# fast_shutdown_v5_0.net
KiCad netlist of a schematic drawn in EAGLE
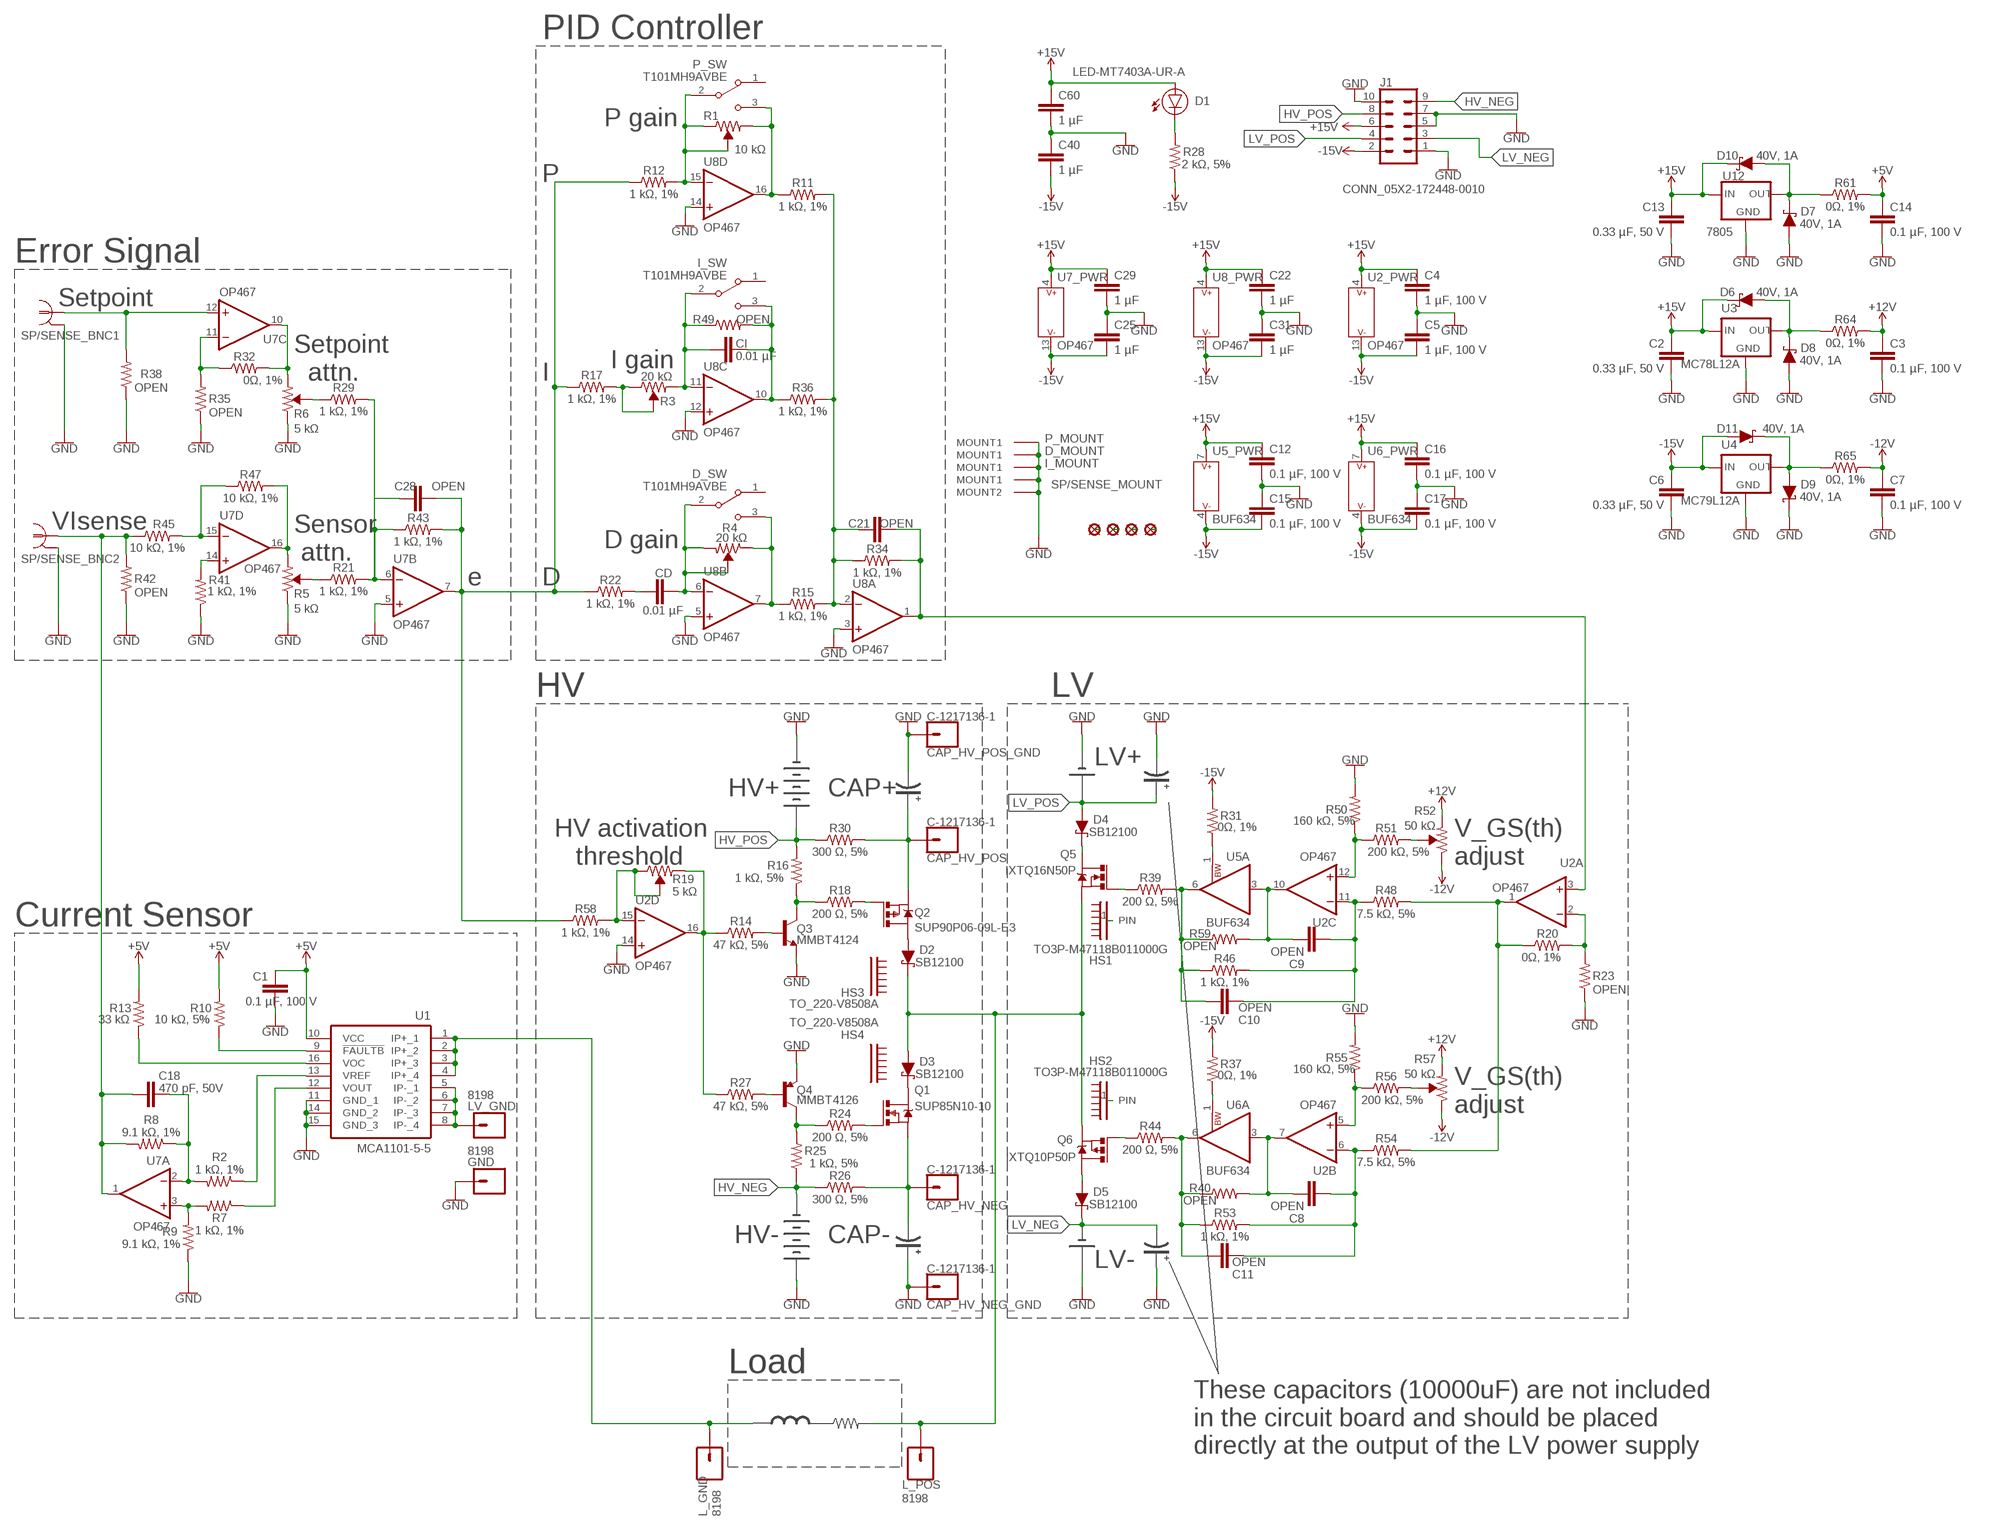
[diagram p0: schematic, sheet 1]

(export (version "E")
  (design (tool "Eeschema 10.0.6"))
  (components
    (comp (ref "C1")
      (value "0.1 µF, 100 V")
      (footprint "eagle-import:C1206")
      (fields (field (name "MFR") "KEMET"))
      (libsource (lib "eagle-import") (part "0.1µF-C1206C104J1RACTU"))
    )
    (comp (ref "C2")
      (value "0.33 µF, 50 V")
      (footprint "eagle-import:C1206")
      (fields (field (name "MFR") "Samsung Electro-Mechanics"))
      (libsource (lib "eagle-import") (part "0.33µF-CL31B334KBFNNNE"))
    )
    (comp (ref "C3")
      (value "0.1 µF, 100 V")
      (footprint "eagle-import:C1206")
      (fields (field (name "MFR") "KEMET"))
      (libsource (lib "eagle-import") (part "0.1µF-C1206C104J1RACTU"))
    )
    (comp (ref "C4")
      (value "1 µF, 100 V")
      (footprint "eagle-import:C1206")
      (fields (field (name "MFR") "KEMET"))
      (libsource (lib "eagle-import") (part "1µF-C1206X105J1RACTU"))
    )
    (comp (ref "C5")
      (value "1 µF, 100 V")
      (footprint "eagle-import:C1206")
      (fields (field (name "MFR") "KEMET"))
      (libsource (lib "eagle-import") (part "1µF-C1206X105J1RACTU"))
    )
    (comp (ref "C6")
      (value "0.33 µF, 50 V")
      (footprint "eagle-import:C1206")
      (fields (field (name "MFR") "Samsung Electro-Mechanics"))
      (libsource (lib "eagle-import") (part "0.33µF-CL31B334KBFNNNE"))
    )
    (comp (ref "C7")
      (value "0.1 µF, 100 V")
      (footprint "eagle-import:C1206")
      (fields (field (name "MFR") "KEMET"))
      (libsource (lib "eagle-import") (part "0.1µF-C1206C104J1RACTU"))
    )
    (comp (ref "C8")
      (value "OPEN")
      (footprint "eagle-import:C1206_OPEN")
      (fields (field (name "MFR") "NA"))
      (libsource (lib "eagle-import") (part "OPEN"))
    )
    (comp (ref "C9")
      (value "OPEN")
      (footprint "eagle-import:C1206_OPEN")
      (fields (field (name "MFR") "NA"))
      (libsource (lib "eagle-import") (part "OPEN"))
    )
    (comp (ref "C10")
      (value "OPEN")
      (footprint "eagle-import:C1206_OPEN")
      (fields (field (name "MFR") "NA"))
      (libsource (lib "eagle-import") (part "OPEN"))
    )
    (comp (ref "C11")
      (value "OPEN")
      (footprint "eagle-import:C1206_OPEN")
      (fields (field (name "MFR") "NA"))
      (libsource (lib "eagle-import") (part "OPEN"))
    )
    (comp (ref "C12")
      (value "0.1 µF, 100 V")
      (footprint "eagle-import:C1206")
      (fields (field (name "MFR") "KEMET"))
      (libsource (lib "eagle-import") (part "0.1µF-C1206C104J1RACTU"))
    )
    (comp (ref "C13")
      (value "0.33 µF, 50 V")
      (footprint "eagle-import:C1206")
      (fields (field (name "MFR") "Samsung Electro-Mechanics"))
      (libsource (lib "eagle-import") (part "0.33µF-CL31B334KBFNNNE"))
    )
    (comp (ref "C14")
      (value "0.1 µF, 100 V")
      (footprint "eagle-import:C1206")
      (fields (field (name "MFR") "KEMET"))
      (libsource (lib "eagle-import") (part "0.1µF-C1206C104J1RACTU"))
    )
    (comp (ref "C15")
      (value "0.1 µF, 100 V")
      (footprint "eagle-import:C1206")
      (fields (field (name "MFR") "KEMET"))
      (libsource (lib "eagle-import") (part "0.1µF-C1206C104J1RACTU"))
    )
    (comp (ref "C16")
      (value "0.1 µF, 100 V")
      (footprint "eagle-import:C1206")
      (fields (field (name "MFR") "KEMET"))
      (libsource (lib "eagle-import") (part "0.1µF-C1206C104J1RACTU"))
    )
    (comp (ref "C17")
      (value "0.1 µF, 100 V")
      (footprint "eagle-import:C1206")
      (fields (field (name "MFR") "KEMET"))
      (libsource (lib "eagle-import") (part "0.1µF-C1206C104J1RACTU"))
    )
    (comp (ref "C18")
      (value "470 pF, 50V")
      (footprint "eagle-import:C1206")
      (fields (field (name "MFR") "KEMET"))
      (libsource (lib "eagle-import") (part "470ρF-C1206C471K5RACTU"))
    )
    (comp (ref "C21")
      (value "OPEN")
      (footprint "eagle-import:C1206_OPEN")
      (fields (field (name "MFR") "NA"))
      (libsource (lib "eagle-import") (part "OPEN"))
    )
    (comp (ref "C22")
      (value "1 µF")
      (footprint "eagle-import:C1206")
      (fields (field (name "MFR") "KEMET"))
      (libsource (lib "eagle-import") (part "1µF-C1206C105K3RACTU"))
    )
    (comp (ref "C25")
      (value "1 µF")
      (footprint "eagle-import:C1206")
      (fields (field (name "MFR") "KEMET"))
      (libsource (lib "eagle-import") (part "1µF-C1206C105K3RACTU"))
    )
    (comp (ref "C28")
      (value "OPEN")
      (footprint "eagle-import:C1206_OPEN")
      (fields (field (name "MFR") "NA"))
      (libsource (lib "eagle-import") (part "OPEN"))
    )
    (comp (ref "C29")
      (value "1 µF")
      (footprint "eagle-import:C1206")
      (fields (field (name "MFR") "KEMET"))
      (libsource (lib "eagle-import") (part "1µF-C1206C105K3RACTU"))
    )
    (comp (ref "C31")
      (value "1 µF")
      (footprint "eagle-import:C1206")
      (fields (field (name "MFR") "KEMET"))
      (libsource (lib "eagle-import") (part "1µF-C1206C105K3RACTU"))
    )
    (comp (ref "C40")
      (value "1 µF")
      (footprint "eagle-import:C1206")
      (fields (field (name "MFR") "KEMET"))
      (libsource (lib "eagle-import") (part "1µF-C1206C105K3RACTU"))
    )
    (comp (ref "C60")
      (value "1 µF")
      (footprint "eagle-import:C1206")
      (fields (field (name "MFR") "KEMET"))
      (libsource (lib "eagle-import") (part "1µF-C1206C105K3RACTU"))
    )
    (comp (ref "CAP_HV_NEG")
      (value "C-1217136-1")
      (footprint "eagle-import:C-1217136-1")
      (fields (field (name "MFR") "AMP - TE CONNECTIVITY"))
      (libsource (lib "eagle-import") (part "C-1217136-1"))
    )
    (comp (ref "CAP_HV_NEG_GND")
      (value "C-1217136-1")
      (footprint "eagle-import:C-1217136-1")
      (fields (field (name "MFR") "AMP - TE CONNECTIVITY"))
      (libsource (lib "eagle-import") (part "C-1217136-1"))
    )
    (comp (ref "CAP_HV_POS")
      (value "C-1217136-1")
      (footprint "eagle-import:C-1217136-1")
      (fields (field (name "MFR") "AMP - TE CONNECTIVITY"))
      (libsource (lib "eagle-import") (part "C-1217136-1"))
    )
    (comp (ref "CAP_HV_POS_GND")
      (value "C-1217136-1")
      (footprint "eagle-import:C-1217136-1")
      (fields (field (name "MFR") "AMP - TE CONNECTIVITY"))
      (libsource (lib "eagle-import") (part "C-1217136-1"))
    )
    (comp (ref "CD")
      (value "0.01 µF")
      (footprint "eagle-import:C1206")
      (fields (field (name "MFR") "KEMET"))
      (libsource (lib "eagle-import") (part "0.01µF-C1206C103K1RACTU"))
    )
    (comp (ref "CI")
      (value "0.01 µF")
      (footprint "eagle-import:C1206")
      (fields (field (name "MFR") "KEMET"))
      (libsource (lib "eagle-import") (part "0.01µF-C1206C103K1RACTU"))
    )
    (comp (ref "D")
      (value "T101MH9AVBE")
      (footprint "eagle-import:T101MH9AVBE")
      (fields (field (name "MFR") "C&K"))
      (libsource (lib "eagle-import") (part "T101MH9AVBE"))
    )
    (comp (ref "D1")
      (value "LED-MT7403A-UR-A")
      (footprint "eagle-import:LED3MM")
      (fields (field (name "MFR") "Marktech Optoelectronics"))
      (libsource (lib "eagle-import") (part "LED-MT7403A-UR-A"))
    )
    (comp (ref "D2")
      (value "SB12100")
      (footprint "eagle-import:D5.4X7.5")
      (fields (field (name "MFR") "Diotec Semiconductor"))
      (libsource (lib "eagle-import") (part "DIODE_SCHOTTKY-SB12100"))
    )
    (comp (ref "D3")
      (value "SB12100")
      (footprint "eagle-import:D5.4X7.5")
      (fields (field (name "MFR") "Diotec Semiconductor"))
      (libsource (lib "eagle-import") (part "DIODE_SCHOTTKY-SB12100"))
    )
    (comp (ref "D4")
      (value "SB12100")
      (footprint "eagle-import:D5.4X7.5")
      (fields (field (name "MFR") "Diotec Semiconductor"))
      (libsource (lib "eagle-import") (part "DIODE_SCHOTTKY-SB12100"))
    )
    (comp (ref "D5")
      (value "SB12100")
      (footprint "eagle-import:D5.4X7.5")
      (fields (field (name "MFR") "Diotec Semiconductor"))
      (libsource (lib "eagle-import") (part "DIODE_SCHOTTKY-SB12100"))
    )
    (comp (ref "D6")
      (value "40V, 1A")
      (footprint "eagle-import:DO-214AC")
      (fields (field (name "MFR") "ROHM Semiconductor"))
      (libsource (lib "eagle-import") (part "DIODE_SCHOTTKY-RB168L-40TFTE25"))
    )
    (comp (ref "D7")
      (value "40V, 1A")
      (footprint "eagle-import:DO-214AC")
      (fields (field (name "MFR") "ROHM Semiconductor"))
      (libsource (lib "eagle-import") (part "DIODE_SCHOTTKY-RB168L-40TFTE25"))
    )
    (comp (ref "D8")
      (value "40V, 1A")
      (footprint "eagle-import:DO-214AC")
      (fields (field (name "MFR") "ROHM Semiconductor"))
      (libsource (lib "eagle-import") (part "DIODE_SCHOTTKY-RB168L-40TFTE25"))
    )
    (comp (ref "D9")
      (value "40V, 1A")
      (footprint "eagle-import:DO-214AC")
      (fields (field (name "MFR") "ROHM Semiconductor"))
      (libsource (lib "eagle-import") (part "DIODE_SCHOTTKY-RB168L-40TFTE25"))
    )
    (comp (ref "D10")
      (value "40V, 1A")
      (footprint "eagle-import:DO-214AC")
      (fields (field (name "MFR") "ROHM Semiconductor"))
      (libsource (lib "eagle-import") (part "DIODE_SCHOTTKY-RB168L-40TFTE25"))
    )
    (comp (ref "D11")
      (value "40V, 1A")
      (footprint "eagle-import:DO-214AC")
      (fields (field (name "MFR") "ROHM Semiconductor"))
      (libsource (lib "eagle-import") (part "DIODE_SCHOTTKY-RB168L-40TFTE25"))
    )
    (comp (ref "GND")
      (value "8198")
      (footprint "eagle-import:8198")
      (fields (field (name "MFR") "Keystone Electronics"))
      (libsource (lib "eagle-import") (part "8198"))
    )
    (comp (ref "HS1")
      (value "TO3P-M47118B011000G")
      (footprint "eagle-import:M47118B011000G")
      (fields (field (name "MFR") "Aavid"))
      (libsource (lib "eagle-import") (part "TO3P-M47118B011000G"))
    )
    (comp (ref "HS2")
      (value "TO3P-M47118B011000G")
      (footprint "eagle-import:M47118B011000G")
      (fields (field (name "MFR") "Aavid"))
      (libsource (lib "eagle-import") (part "TO3P-M47118B011000G"))
    )
    (comp (ref "HS3")
      (value "TO_220-V8508A")
      (footprint "eagle-import:V8508A")
      (fields (field (name "MFR") "Assmann WSW Components"))
      (libsource (lib "eagle-import") (part "TO_220-V8508A"))
    )
    (comp (ref "HS4")
      (value "TO_220-V8508A")
      (footprint "eagle-import:V8508A")
      (fields (field (name "MFR") "Assmann WSW Components"))
      (libsource (lib "eagle-import") (part "TO_220-V8508A"))
    )
    (comp (ref "I")
      (value "T101MH9AVBE")
      (footprint "eagle-import:T101MH9AVBE")
      (fields (field (name "MFR") "C&K"))
      (libsource (lib "eagle-import") (part "T101MH9AVBE"))
    )
    (comp (ref "J1")
      (value "CONN_05X2-172448-0010")
      (footprint "eagle-import:1724480010")
      (fields (field (name "MFR") "Molex"))
      (libsource (lib "eagle-import") (part "CONN_05X2-172448-0010"))
    )
    (comp (ref "LV_GND")
      (value "8198")
      (footprint "eagle-import:8198")
      (fields (field (name "MFR") "Keystone Electronics"))
      (libsource (lib "eagle-import") (part "8198"))
    )
    (comp (ref "L_GND")
      (value "8198")
      (footprint "eagle-import:8198")
      (fields (field (name "MFR") "Keystone Electronics"))
      (libsource (lib "eagle-import") (part "8198"))
    )
    (comp (ref "L_POS")
      (value "8198")
      (footprint "eagle-import:8198")
      (fields (field (name "MFR") "Keystone Electronics"))
      (libsource (lib "eagle-import") (part "8198"))
    )
    (comp (ref "P")
      (value "T101MH9AVBE")
      (footprint "eagle-import:T101MH9AVBE")
      (fields (field (name "MFR") "C&K"))
      (libsource (lib "eagle-import") (part "T101MH9AVBE"))
    )
    (comp (ref "P1")
      (value "PAD-M3.0")
      (footprint "eagle-import:PAD_M3.0")
      (libsource (lib "eagle-import") (part "PAD-M3.0"))
    )
    (comp (ref "P2")
      (value "PAD-M3.0")
      (footprint "eagle-import:PAD_M3.0")
      (libsource (lib "eagle-import") (part "PAD-M3.0"))
    )
    (comp (ref "P3")
      (value "PAD-M3.0")
      (footprint "eagle-import:PAD_M3.0")
      (libsource (lib "eagle-import") (part "PAD-M3.0"))
    )
    (comp (ref "P4")
      (value "PAD-M3.0")
      (footprint "eagle-import:PAD_M3.0")
      (libsource (lib "eagle-import") (part "PAD-M3.0"))
    )
    (comp (ref "Q1")
      (value "SUP85N10-10")
      (footprint "eagle-import:TO220AB_BL")
      (fields (field (name "MFR") "Vishay / Siliconix"))
      (libsource (lib "eagle-import") (part "MOSFET_N-SUP85N10-10-GE3"))
    )
    (comp (ref "Q2")
      (value "SUP90P06-09L-E3")
      (footprint "eagle-import:TO220AB_BL")
      (fields (field (name "MFR") "Vishay Semiconductors"))
      (libsource (lib "eagle-import") (part "MOSFET_P-SUP90P06-09L-E3"))
    )
    (comp (ref "Q3")
      (value "MMBT4124")
      (footprint "eagle-import:SOT23")
      (fields (field (name "MFR") "onsemi"))
      (libsource (lib "eagle-import") (part "BJT_NPN-MMBT4124LT1G"))
    )
    (comp (ref "Q4")
      (value "MMBT4126")
      (footprint "eagle-import:SOT23")
      (fields (field (name "MFR") "onsemi"))
      (libsource (lib "eagle-import") (part "BJT_PNP-MMBT4126LT1G"))
    )
    (comp (ref "Q5")
      (value "IXTQ16N50P")
      (footprint "eagle-import:TO3P")
      (fields (field (name "MFR") "IXYS"))
      (libsource (lib "eagle-import") (part "MOSFET_N-IXTQ16N50P"))
    )
    (comp (ref "Q6")
      (value "IXTQ10P50P")
      (footprint "eagle-import:TO3P")
      (fields (field (name "MFR") "IXYS"))
      (libsource (lib "eagle-import") (part "MOSFET_P-IXTQ10P50P"))
    )
    (comp (ref "R1")
      (value "10 kΩ")
      (footprint "eagle-import:POT_3006P")
      (fields (field (name "MFR") "Bourns Inc."))
      (libsource (lib "eagle-import") (part "TRIMMER_3006P-10K"))
    )
    (comp (ref "R2")
      (value "1 kΩ, 1%")
      (footprint "eagle-import:R1206")
      (fields (field (name "MFR") "Yageo"))
      (libsource (lib "eagle-import") (part "1KΩ-RC1206FR-071KL"))
    )
    (comp (ref "R3")
      (value "20 kΩ")
      (footprint "eagle-import:POT_3006P")
      (fields (field (name "MFR") "Bourns Inc."))
      (libsource (lib "eagle-import") (part "TRIMMER_3006P-20K"))
    )
    (comp (ref "R4")
      (value "20 kΩ")
      (footprint "eagle-import:POT_3006P")
      (fields (field (name "MFR") "Bourns Inc."))
      (libsource (lib "eagle-import") (part "TRIMMER_3006P-20K"))
    )
    (comp (ref "R5")
      (value "5 kΩ")
      (footprint "eagle-import:POT_3006P")
      (fields (field (name "MFR") "Bourns Inc."))
      (libsource (lib "eagle-import") (part "TRIMMER_3006P-5K"))
    )
    (comp (ref "R6")
      (value "5 kΩ")
      (footprint "eagle-import:POT_3006P")
      (fields (field (name "MFR") "Bourns Inc."))
      (libsource (lib "eagle-import") (part "TRIMMER_3006P-5K"))
    )
    (comp (ref "R7")
      (value "1 kΩ, 1%")
      (footprint "eagle-import:R1206")
      (fields (field (name "MFR") "Yageo"))
      (libsource (lib "eagle-import") (part "1KΩ-RC1206FR-071KL"))
    )
    (comp (ref "R8")
      (value "9.1 kΩ, 1%")
      (footprint "eagle-import:R1206")
      (fields (field (name "MFR") "Yageo"))
      (libsource (lib "eagle-import") (part "9.1KΩ-RC1206FR-079K1L"))
    )
    (comp (ref "R9")
      (value "9.1 kΩ, 1%")
      (footprint "eagle-import:R1206")
      (fields (field (name "MFR") "Yageo"))
      (libsource (lib "eagle-import") (part "9.1KΩ-RC1206FR-079K1L"))
    )
    (comp (ref "R10")
      (value "10 kΩ, 5%")
      (footprint "eagle-import:R1206")
      (fields (field (name "MFR") "Yageo"))
      (libsource (lib "eagle-import") (part "10KΩ-RC1206JR-0710KL"))
    )
    (comp (ref "R11")
      (value "1 kΩ, 1%")
      (footprint "eagle-import:R1206")
      (fields (field (name "MFR") "Yageo"))
      (libsource (lib "eagle-import") (part "1KΩ-RC1206FR-071KL"))
    )
    (comp (ref "R12")
      (value "1 kΩ, 1%")
      (footprint "eagle-import:R1206")
      (fields (field (name "MFR") "Yageo"))
      (libsource (lib "eagle-import") (part "1KΩ-RC1206FR-071KL"))
    )
    (comp (ref "R13")
      (value "33 kΩ")
      (footprint "eagle-import:R1206")
      (libsource (lib "eagle-import") (part "NOVA"))
    )
    (comp (ref "R14")
      (value "47 kΩ, 5%")
      (footprint "eagle-import:R1206")
      (fields (field (name "MFR") "YAGEO"))
      (libsource (lib "eagle-import") (part "47KΩ-RC1206JR-0747KL"))
    )
    (comp (ref "R15")
      (value "1 kΩ, 1%")
      (footprint "eagle-import:R1206")
      (fields (field (name "MFR") "Yageo"))
      (libsource (lib "eagle-import") (part "1KΩ-RC1206FR-071KL"))
    )
    (comp (ref "R16")
      (value "1 kΩ, 5%")
      (footprint "eagle-import:R1206")
      (fields (field (name "MFR") "Yageo"))
      (libsource (lib "eagle-import") (part "1KΩ-RC1206JR-071KL"))
    )
    (comp (ref "R17")
      (value "1 kΩ, 1%")
      (footprint "eagle-import:R1206")
      (fields (field (name "MFR") "Yageo"))
      (libsource (lib "eagle-import") (part "1KΩ-RC1206FR-071KL"))
    )
    (comp (ref "R18")
      (value "200 Ω, 5%")
      (footprint "eagle-import:R1206")
      (fields (field (name "MFR") "YAGEO"))
      (libsource (lib "eagle-import") (part "200Ω-RC1206JR-07200RL"))
    )
    (comp (ref "R19")
      (value "5 kΩ")
      (footprint "eagle-import:POT_3006P")
      (fields (field (name "MFR") "Bourns Inc."))
      (libsource (lib "eagle-import") (part "TRIMMER_3006P-5K"))
    )
    (comp (ref "R20")
      (value "0Ω, 1%")
      (footprint "eagle-import:R1206")
      (fields (field (name "MFR") "YAGEO"))
      (libsource (lib "eagle-import") (part "0Ω-RC1206FR-070RL"))
    )
    (comp (ref "R21")
      (value "1 kΩ, 1%")
      (footprint "eagle-import:R1206")
      (fields (field (name "MFR") "Yageo"))
      (libsource (lib "eagle-import") (part "1KΩ-RC1206FR-071KL"))
    )
    (comp (ref "R22")
      (value "1 kΩ, 1%")
      (footprint "eagle-import:R1206")
      (fields (field (name "MFR") "Yageo"))
      (libsource (lib "eagle-import") (part "1KΩ-RC1206FR-071KL"))
    )
    (comp (ref "R23")
      (value "OPEN")
      (footprint "eagle-import:R1206_OPEN")
      (fields (field (name "MFR") "NA"))
      (libsource (lib "eagle-import") (part "OPEN-1206"))
    )
    (comp (ref "R24")
      (value "200 Ω, 5%")
      (footprint "eagle-import:R1206")
      (fields (field (name "MFR") "YAGEO"))
      (libsource (lib "eagle-import") (part "200Ω-RC1206JR-07200RL"))
    )
    (comp (ref "R25")
      (value "1 kΩ, 5%")
      (footprint "eagle-import:R1206")
      (fields (field (name "MFR") "Yageo"))
      (libsource (lib "eagle-import") (part "1KΩ-RC1206JR-071KL"))
    )
    (comp (ref "R26")
      (value "300 Ω, 5%")
      (footprint "eagle-import:R1206")
      (fields (field (name "MFR") "Yageo"))
      (libsource (lib "eagle-import") (part "300Ω-RC1206JR-07300RL"))
    )
    (comp (ref "R27")
      (value "47 kΩ, 5%")
      (footprint "eagle-import:R1206")
      (fields (field (name "MFR") "YAGEO"))
      (libsource (lib "eagle-import") (part "47KΩ-RC1206JR-0747KL"))
    )
    (comp (ref "R28")
      (value "2 kΩ, 5%")
      (footprint "eagle-import:R1206")
      (fields (field (name "MFR") "YAGEO"))
      (libsource (lib "eagle-import") (part "2KΩ-RC1206JR-072KL"))
    )
    (comp (ref "R29")
      (value "1 kΩ, 1%")
      (footprint "eagle-import:R1206")
      (fields (field (name "MFR") "Yageo"))
      (libsource (lib "eagle-import") (part "1KΩ-RC1206FR-071KL"))
    )
    (comp (ref "R30")
      (value "300 Ω, 5%")
      (footprint "eagle-import:R1206")
      (fields (field (name "MFR") "Yageo"))
      (libsource (lib "eagle-import") (part "300Ω-RC1206JR-07300RL"))
    )
    (comp (ref "R31")
      (value "0Ω, 1%")
      (footprint "eagle-import:R1206")
      (fields (field (name "MFR") "YAGEO"))
      (libsource (lib "eagle-import") (part "0Ω-RC1206FR-070RL"))
    )
    (comp (ref "R32")
      (value "0Ω, 1%")
      (footprint "eagle-import:R1206")
      (fields (field (name "MFR") "YAGEO"))
      (libsource (lib "eagle-import") (part "0Ω-RC1206FR-070RL"))
    )
    (comp (ref "R34")
      (value "1 kΩ, 1%")
      (footprint "eagle-import:R1206")
      (fields (field (name "MFR") "Yageo"))
      (libsource (lib "eagle-import") (part "1KΩ-RC1206FR-071KL"))
    )
    (comp (ref "R35")
      (value "OPEN")
      (footprint "eagle-import:R1206_OPEN")
      (fields (field (name "MFR") "NA"))
      (libsource (lib "eagle-import") (part "OPEN-1206"))
    )
    (comp (ref "R36")
      (value "1 kΩ, 1%")
      (footprint "eagle-import:R1206")
      (fields (field (name "MFR") "Yageo"))
      (libsource (lib "eagle-import") (part "1KΩ-RC1206FR-071KL"))
    )
    (comp (ref "R37")
      (value "0Ω, 1%")
      (footprint "eagle-import:R1206")
      (fields (field (name "MFR") "YAGEO"))
      (libsource (lib "eagle-import") (part "0Ω-RC1206FR-070RL"))
    )
    (comp (ref "R38")
      (value "OPEN")
      (footprint "eagle-import:R1206_OPEN")
      (fields (field (name "MFR") "NA"))
      (libsource (lib "eagle-import") (part "OPEN-1206"))
    )
    (comp (ref "R39")
      (value "200 Ω, 5%")
      (footprint "eagle-import:R1206")
      (fields (field (name "MFR") "YAGEO"))
      (libsource (lib "eagle-import") (part "200Ω-RC1206JR-07200RL"))
    )
    (comp (ref "R40")
      (value "OPEN")
      (footprint "eagle-import:R1206_OPEN")
      (fields (field (name "MFR") "NA"))
      (libsource (lib "eagle-import") (part "OPEN-1206"))
    )
    (comp (ref "R41")
      (value "1 kΩ, 1%")
      (footprint "eagle-import:R1206")
      (fields (field (name "MFR") "Yageo"))
      (libsource (lib "eagle-import") (part "1KΩ-RC1206FR-071KL"))
    )
    (comp (ref "R42")
      (value "OPEN")
      (footprint "eagle-import:R1206_OPEN")
      (fields (field (name "MFR") "NA"))
      (libsource (lib "eagle-import") (part "OPEN-1206"))
    )
    (comp (ref "R43")
      (value "1 kΩ, 1%")
      (footprint "eagle-import:R1206")
      (fields (field (name "MFR") "Yageo"))
      (libsource (lib "eagle-import") (part "1KΩ-RC1206FR-071KL"))
    )
    (comp (ref "R44")
      (value "200 Ω, 5%")
      (footprint "eagle-import:R1206")
      (fields (field (name "MFR") "YAGEO"))
      (libsource (lib "eagle-import") (part "200Ω-RC1206JR-07200RL"))
    )
    (comp (ref "R45")
      (value "10 kΩ, 1%")
      (footprint "eagle-import:R1206")
      (fields (field (name "MFR") "Yageo"))
      (libsource (lib "eagle-import") (part "10KΩ-RC1206FR-0710KL"))
    )
    (comp (ref "R46")
      (value "1 kΩ, 1%")
      (footprint "eagle-import:R1206")
      (fields (field (name "MFR") "Yageo"))
      (libsource (lib "eagle-import") (part "1KΩ-RC1206FR-071KL"))
    )
    (comp (ref "R47")
      (value "10 kΩ, 1%")
      (footprint "eagle-import:R1206")
      (fields (field (name "MFR") "Yageo"))
      (libsource (lib "eagle-import") (part "10KΩ-RC1206FR-0710KL"))
    )
    (comp (ref "R48")
      (value "7.5 kΩ, 5%")
      (footprint "eagle-import:R1206")
      (fields (field (name "MFR") "Yageo"))
      (libsource (lib "eagle-import") (part "7.5KΩ-RC1206JR-077K5L"))
    )
    (comp (ref "R49")
      (value "OPEN")
      (footprint "eagle-import:R1206_OPEN")
      (fields (field (name "MFR") "NA"))
      (libsource (lib "eagle-import") (part "OPEN-1206"))
    )
    (comp (ref "R50")
      (value "160 kΩ, 5%")
      (footprint "eagle-import:R1206")
      (fields (field (name "MFR") "YAGEO"))
      (libsource (lib "eagle-import") (part "160KΩ-RC1206JR-07160KL"))
    )
    (comp (ref "R51")
      (value "200 kΩ, 5%")
      (footprint "eagle-import:R1206")
      (fields (field (name "MFR") "YAGEO"))
      (libsource (lib "eagle-import") (part "200KΩ-RC1206JR-07200KL"))
    )
    (comp (ref "R52")
      (value "50 kΩ")
      (footprint "eagle-import:POT_3006P")
      (fields (field (name "MFR") "Bourns Inc."))
      (libsource (lib "eagle-import") (part "TRIMMER_3006P-50K"))
    )
    (comp (ref "R53")
      (value "1 kΩ, 1%")
      (footprint "eagle-import:R1206")
      (fields (field (name "MFR") "Yageo"))
      (libsource (lib "eagle-import") (part "1KΩ-RC1206FR-071KL"))
    )
    (comp (ref "R54")
      (value "7.5 kΩ, 5%")
      (footprint "eagle-import:R1206")
      (fields (field (name "MFR") "Yageo"))
      (libsource (lib "eagle-import") (part "7.5KΩ-RC1206JR-077K5L"))
    )
    (comp (ref "R55")
      (value "160 kΩ, 5%")
      (footprint "eagle-import:R1206")
      (fields (field (name "MFR") "YAGEO"))
      (libsource (lib "eagle-import") (part "160KΩ-RC1206JR-07160KL"))
    )
    (comp (ref "R56")
      (value "200 kΩ, 5%")
      (footprint "eagle-import:R1206")
      (fields (field (name "MFR") "YAGEO"))
      (libsource (lib "eagle-import") (part "200KΩ-RC1206JR-07200KL"))
    )
    (comp (ref "R57")
      (value "50 kΩ")
      (footprint "eagle-import:POT_3006P")
      (fields (field (name "MFR") "Bourns Inc."))
      (libsource (lib "eagle-import") (part "TRIMMER_3006P-50K"))
    )
    (comp (ref "R58")
      (value "1 kΩ, 1%")
      (footprint "eagle-import:R1206")
      (fields (field (name "MFR") "Yageo"))
      (libsource (lib "eagle-import") (part "1KΩ-RC1206FR-071KL"))
    )
    (comp (ref "R59")
      (value "OPEN")
      (footprint "eagle-import:R1206_OPEN")
      (fields (field (name "MFR") "NA"))
      (libsource (lib "eagle-import") (part "OPEN-1206"))
    )
    (comp (ref "R61")
      (value "0Ω, 1%")
      (footprint "eagle-import:R1206")
      (fields (field (name "MFR") "YAGEO"))
      (libsource (lib "eagle-import") (part "0Ω-RC1206FR-070RL"))
    )
    (comp (ref "R64")
      (value "0Ω, 1%")
      (footprint "eagle-import:R1206")
      (fields (field (name "MFR") "YAGEO"))
      (libsource (lib "eagle-import") (part "0Ω-RC1206FR-070RL"))
    )
    (comp (ref "R65")
      (value "0Ω, 1%")
      (footprint "eagle-import:R1206")
      (fields (field (name "MFR") "YAGEO"))
      (libsource (lib "eagle-import") (part "0Ω-RC1206FR-070RL"))
    )
    (comp (ref "SP/SENSE")
      (value "BNC2_CHG-5227161-1")
      (footprint "eagle-import:5227161-1_CHG")
      (fields (field (name "MFR") "TE Connectivity AMP Connectors"))
      (libsource (lib "eagle-import") (part "BNC2_CHG-5227161-1"))
    )
    (comp (ref "U1")
      (value "MCA1101-5-5")
      (footprint "eagle-import:SOIC16-W")
      (fields (field (name "MFR") "ACEINNA"))
      (libsource (lib "eagle-import") (part "MCA1101-5-5-MCA1101-5-5"))
    )
    (comp (ref "U2")
      (value "OP467")
      (footprint "eagle-import:SOIC16-W")
      (fields (field (name "MFR") "Analog Devices Inc."))
      (libsource (lib "eagle-import") (part "OP467-OP467GSZ"))
    )
    (comp (ref "U3")
      (value "MC78L12A")
      (footprint "eagle-import:SOIC8-N")
      (fields (field (name "MFR") "onsemi"))
      (libsource (lib "eagle-import") (part "MC78L12A-MC78L12ABDR2G"))
    )
    (comp (ref "U4")
      (value "MC79L12A")
      (footprint "eagle-import:SOIC8-N")
      (fields (field (name "MFR") "onsemi"))
      (libsource (lib "eagle-import") (part "MC79L12A-MC79L12ABDR2G"))
    )
    (comp (ref "U5")
      (value "BUF634")
      (footprint "eagle-import:SOIC8-N")
      (fields (field (name "MFR") "Texas Instruments"))
      (libsource (lib "eagle-import") (part "BUF634-BUF634AIDR"))
    )
    (comp (ref "U6")
      (value "BUF634")
      (footprint "eagle-import:SOIC8-N")
      (fields (field (name "MFR") "Texas Instruments"))
      (libsource (lib "eagle-import") (part "BUF634-BUF634AIDR"))
    )
    (comp (ref "U7")
      (value "OP467")
      (footprint "eagle-import:SOIC16-W")
      (fields (field (name "MFR") "Analog Devices Inc."))
      (libsource (lib "eagle-import") (part "OP467-OP467GSZ"))
    )
    (comp (ref "U8")
      (value "OP467")
      (footprint "eagle-import:SOIC16-W")
      (fields (field (name "MFR") "Analog Devices Inc."))
      (libsource (lib "eagle-import") (part "OP467-OP467GSZ"))
    )
    (comp (ref "U12")
      (value "7805")
      (footprint "eagle-import:DPAK")
      (fields (field (name "MFR") "STMicroelectronics"))
      (libsource (lib "eagle-import") (part "MC7805CT-L7805CDT-TR"))
    )
  )
  (nets
    (net (code "1") (name "+5V") (class "Default")
      (node (ref "C1") (pin "1") (pinfunction "1_1") (pintype "passive"))
      (node (ref "C14") (pin "1") (pinfunction "1_1") (pintype "passive"))
      (node (ref "R10") (pin "2") (pinfunction "2_2") (pintype "passive"))
      (node (ref "R13") (pin "2") (pinfunction "2_2") (pintype "passive"))
      (node (ref "R61") (pin "2") (pinfunction "2_2") (pintype "passive"))
      (node (ref "U1") (pin "10") (pinfunction "VCC_10") (pintype "bidirectional"))
    )
    (net (code "2") (name "+12V") (class "Default")
      (node (ref "C3") (pin "1") (pinfunction "1_1") (pintype "passive"))
      (node (ref "R52") (pin "1") (pinfunction "CCW_1") (pintype "passive"))
      (node (ref "R57") (pin "1") (pinfunction "CCW_1") (pintype "passive"))
      (node (ref "R64") (pin "2") (pinfunction "2_2") (pintype "passive"))
    )
    (net (code "3") (name "+15V") (class "Default")
      (node (ref "C12") (pin "1") (pinfunction "1_1") (pintype "passive"))
      (node (ref "C13") (pin "1") (pinfunction "1_1") (pintype "passive"))
      (node (ref "C16") (pin "1") (pinfunction "1_1") (pintype "passive"))
      (node (ref "C2") (pin "1") (pinfunction "1_1") (pintype "passive"))
      (node (ref "C22") (pin "1") (pinfunction "1_1") (pintype "passive"))
      (node (ref "C29") (pin "1") (pinfunction "1_1") (pintype "passive"))
      (node (ref "C4") (pin "1") (pinfunction "1_1") (pintype "passive"))
      (node (ref "C60") (pin "1") (pinfunction "1_1") (pintype "passive"))
      (node (ref "D1") (pin "A") (pinfunction "A_A") (pintype "passive"))
      (node (ref "D10") (pin "K") (pinfunction "C_K") (pintype "passive"))
      (node (ref "D6") (pin "K") (pinfunction "C_K") (pintype "passive"))
      (node (ref "J1") (pin "6") (pinfunction "6_6") (pintype "passive"))
      (node (ref "U12") (pin "1") (pinfunction "IN_1") (pintype "input"))
      (node (ref "U2") (pin "4") (pinfunction "P$V+_4") (pintype "bidirectional"))
      (node (ref "U3") (pin "8") (pinfunction "IN_8") (pintype "input"))
      (node (ref "U5") (pin "7") (pinfunction "P$V+_7") (pintype "bidirectional"))
      (node (ref "U6") (pin "7") (pinfunction "P$V+_7") (pintype "bidirectional"))
      (node (ref "U7") (pin "4") (pinfunction "P$V+_4") (pintype "bidirectional"))
      (node (ref "U8") (pin "4") (pinfunction "P$V+_4") (pintype "bidirectional"))
    )
    (net (code "4") (name "-12V") (class "Default")
      (node (ref "C7") (pin "1") (pinfunction "1_1") (pintype "passive"))
      (node (ref "R52") (pin "3") (pinfunction "CW_3") (pintype "passive"))
      (node (ref "R57") (pin "3") (pinfunction "CW_3") (pintype "passive"))
      (node (ref "R65") (pin "2") (pinfunction "2_2") (pintype "passive"))
    )
    (net (code "5") (name "-15V") (class "Default")
      (node (ref "C15") (pin "2") (pinfunction "2_2") (pintype "passive"))
      (node (ref "C17") (pin "2") (pinfunction "2_2") (pintype "passive"))
      (node (ref "C25") (pin "2") (pinfunction "2_2") (pintype "passive"))
      (node (ref "C31") (pin "2") (pinfunction "2_2") (pintype "passive"))
      (node (ref "C40") (pin "2") (pinfunction "2_2") (pintype "passive"))
      (node (ref "C5") (pin "2") (pinfunction "2_2") (pintype "passive"))
      (node (ref "C6") (pin "1") (pinfunction "1_1") (pintype "passive"))
      (node (ref "D11") (pin "A") (pinfunction "A_A") (pintype "passive"))
      (node (ref "J1") (pin "2") (pinfunction "2_2") (pintype "passive"))
      (node (ref "R28") (pin "1") (pinfunction "1_1") (pintype "passive"))
      (node (ref "R31") (pin "2") (pinfunction "2_2") (pintype "passive"))
      (node (ref "R37") (pin "2") (pinfunction "2_2") (pintype "passive"))
      (node (ref "U2") (pin "13") (pinfunction "P$V-_13") (pintype "bidirectional"))
      (node (ref "U4") (pin "2") (pinfunction "IN_2") (pintype "input"))
      (node (ref "U4") (pin "3") (pinfunction "IN_3") (pintype "input"))
      (node (ref "U4") (pin "6") (pinfunction "IN_6") (pintype "input"))
      (node (ref "U4") (pin "7") (pinfunction "IN_7") (pintype "input"))
      (node (ref "U5") (pin "4") (pinfunction "P$V-_4") (pintype "bidirectional"))
      (node (ref "U6") (pin "4") (pinfunction "P$V-_4") (pintype "bidirectional"))
      (node (ref "U7") (pin "13") (pinfunction "P$V-_13") (pintype "bidirectional"))
      (node (ref "U8") (pin "13") (pinfunction "P$V-_13") (pintype "bidirectional"))
    )
    (net (code "6") (name "GND") (class "Default")
      (node (ref "C1") (pin "2") (pinfunction "2_2") (pintype "passive"))
      (node (ref "C12") (pin "2") (pinfunction "2_2") (pintype "passive"))
      (node (ref "C13") (pin "2") (pinfunction "2_2") (pintype "passive"))
      (node (ref "C14") (pin "2") (pinfunction "2_2") (pintype "passive"))
      (node (ref "C15") (pin "1") (pinfunction "1_1") (pintype "passive"))
      (node (ref "C16") (pin "2") (pinfunction "2_2") (pintype "passive"))
      (node (ref "C17") (pin "1") (pinfunction "1_1") (pintype "passive"))
      (node (ref "C2") (pin "2") (pinfunction "2_2") (pintype "passive"))
      (node (ref "C22") (pin "2") (pinfunction "2_2") (pintype "passive"))
      (node (ref "C25") (pin "1") (pinfunction "1_1") (pintype "passive"))
      (node (ref "C29") (pin "2") (pinfunction "2_2") (pintype "passive"))
      (node (ref "C3") (pin "2") (pinfunction "2_2") (pintype "passive"))
      (node (ref "C31") (pin "1") (pinfunction "1_1") (pintype "passive"))
      (node (ref "C4") (pin "2") (pinfunction "2_2") (pintype "passive"))
      (node (ref "C40") (pin "1") (pinfunction "1_1") (pintype "passive"))
      (node (ref "C5") (pin "1") (pinfunction "1_1") (pintype "passive"))
      (node (ref "C6") (pin "2") (pinfunction "2_2") (pintype "passive"))
      (node (ref "C60") (pin "2") (pinfunction "2_2") (pintype "passive"))
      (node (ref "C7") (pin "2") (pinfunction "2_2") (pintype "passive"))
      (node (ref "CAP_HV_NEG_GND") (pin "1") (pinfunction "1_1") (pintype "passive"))
      (node (ref "CAP_HV_NEG_GND") (pin "2") (pinfunction "1_2") (pintype "passive"))
      (node (ref "CAP_HV_POS_GND") (pin "1") (pinfunction "1_1") (pintype "passive"))
      (node (ref "CAP_HV_POS_GND") (pin "2") (pinfunction "1_2") (pintype "passive"))
      (node (ref "D") (pin "H1") (pinfunction "MOUNT1_H1") (pintype "passive"))
      (node (ref "D7") (pin "A") (pinfunction "A_A") (pintype "passive"))
      (node (ref "D8") (pin "A") (pinfunction "A_A") (pintype "passive"))
      (node (ref "D9") (pin "K") (pinfunction "C_K") (pintype "passive"))
      (node (ref "GND") (pin "1") (pinfunction "1_1") (pintype "passive"))
      (node (ref "GND") (pin "2") (pinfunction "1_2") (pintype "passive"))
      (node (ref "I") (pin "H1") (pinfunction "MOUNT1_H1") (pintype "passive"))
      (node (ref "J1") (pin "1") (pinfunction "1_1") (pintype "passive"))
      (node (ref "J1") (pin "10") (pinfunction "10_10") (pintype "passive"))
      (node (ref "J1") (pin "5") (pinfunction "5_5") (pintype "passive"))
      (node (ref "J1") (pin "7") (pinfunction "7_7") (pintype "passive"))
      (node (ref "P") (pin "H1") (pinfunction "MOUNT1_H1") (pintype "passive"))
      (node (ref "Q3") (pin "2") (pinfunction "E_2") (pintype "passive"))
      (node (ref "Q4") (pin "2") (pinfunction "E_2") (pintype "passive"))
      (node (ref "R23") (pin "1") (pinfunction "1_1") (pintype "passive"))
      (node (ref "R35") (pin "1") (pinfunction "1_1") (pintype "passive"))
      (node (ref "R38") (pin "1") (pinfunction "1_1") (pintype "passive"))
      (node (ref "R41") (pin "1") (pinfunction "1_1") (pintype "passive"))
      (node (ref "R42") (pin "1") (pinfunction "1_1") (pintype "passive"))
      (node (ref "R5") (pin "3") (pinfunction "CW_3") (pintype "passive"))
      (node (ref "R50") (pin "2") (pinfunction "2_2") (pintype "passive"))
      (node (ref "R55") (pin "2") (pinfunction "2_2") (pintype "passive"))
      (node (ref "R6") (pin "3") (pinfunction "CW_3") (pintype "passive"))
      (node (ref "R9") (pin "1") (pinfunction "1_1") (pintype "passive"))
      (node (ref "SP/SENSE") (pin "2") (pinfunction "2_2") (pintype "passive"))
      (node (ref "SP/SENSE") (pin "4") (pinfunction "2_4") (pintype "passive"))
      (node (ref "SP/SENSE") (pin "H1") (pinfunction "MOUNT1_H1") (pintype "passive"))
      (node (ref "SP/SENSE") (pin "H2") (pinfunction "MOUNT2_H2") (pintype "passive"))
      (node (ref "SP/SENSE") (pin "H3") (pinfunction "MOUNT1_H3") (pintype "passive"))
      (node (ref "SP/SENSE") (pin "H5") (pinfunction "MOUNT1_H5") (pintype "passive"))
      (node (ref "SP/SENSE") (pin "H6") (pinfunction "MOUNT2_H6") (pintype "passive"))
      (node (ref "U1") (pin "11") (pinfunction "GND_1_11") (pintype "bidirectional"))
      (node (ref "U1") (pin "14") (pinfunction "GND_2_14") (pintype "bidirectional"))
      (node (ref "U1") (pin "15") (pinfunction "GND_3_15") (pintype "bidirectional"))
      (node (ref "U12") (pin "4") (pinfunction "GND_4") (pintype "input"))
      (node (ref "U2") (pin "14") (pinfunction "+IN_14") (pintype "input"))
      (node (ref "U3") (pin "2") (pinfunction "GND_2") (pintype "input"))
      (node (ref "U3") (pin "3") (pinfunction "GND_3") (pintype "input"))
      (node (ref "U3") (pin "6") (pinfunction "GND_6") (pintype "input"))
      (node (ref "U3") (pin "7") (pinfunction "GND_7") (pintype "input"))
      (node (ref "U4") (pin "5") (pinfunction "GND_5") (pintype "input"))
      (node (ref "U7") (pin "5") (pinfunction "+IN_5") (pintype "input"))
      (node (ref "U8") (pin "12") (pinfunction "+IN_12") (pintype "input"))
      (node (ref "U8") (pin "14") (pinfunction "+IN_14") (pintype "input"))
      (node (ref "U8") (pin "3") (pinfunction "+IN_3") (pintype "input"))
      (node (ref "U8") (pin "5") (pinfunction "+IN_5") (pintype "input"))
    )
    (net (code "7") (name "HV_NEG") (class "Default")
      (node (ref "J1") (pin "9") (pinfunction "9_9") (pintype "passive"))
      (node (ref "R25") (pin "1") (pinfunction "1_1") (pintype "passive"))
      (node (ref "R26") (pin "1") (pinfunction "1_1") (pintype "passive"))
    )
    (net (code "8") (name "HV_POS") (class "Default")
      (node (ref "J1") (pin "8") (pinfunction "8_8") (pintype "passive"))
      (node (ref "R16") (pin "2") (pinfunction "2_2") (pintype "passive"))
      (node (ref "R30") (pin "1") (pinfunction "1_1") (pintype "passive"))
    )
    (net (code "9") (name "LV_NEG") (class "Default")
      (node (ref "D5") (pin "1") (pinfunction "C_1") (pintype "passive"))
      (node (ref "J1") (pin "3") (pinfunction "3_3") (pintype "passive"))
    )
    (net (code "10") (name "LV_POS") (class "Default")
      (node (ref "D4") (pin "2") (pinfunction "A_2") (pintype "passive"))
      (node (ref "J1") (pin "4") (pinfunction "4_4") (pintype "passive"))
    )
    (net (code "11") (name "Net-(CD-Pad1)") (class "Default")
      (node (ref "CD") (pin "1") (pinfunction "1_1") (pintype "passive"))
      (node (ref "R22") (pin "2") (pinfunction "2_2") (pintype "passive"))
    )
    (net (code "12") (name "Net-(D1-C)") (class "Default")
      (node (ref "D1") (pin "K") (pinfunction "C_K") (pintype "passive"))
      (node (ref "R28") (pin "2") (pinfunction "2_2") (pintype "passive"))
    )
    (net (code "13") (name "Net-(D2-A)") (class "Default")
      (node (ref "D2") (pin "2") (pinfunction "A_2") (pintype "passive"))
      (node (ref "Q2") (pin "2") (pinfunction "D_2") (pintype "bidirectional"))
    )
    (net (code "14") (name "Net-(D2-C)") (class "Default")
      (node (ref "D2") (pin "1") (pinfunction "C_1") (pintype "passive"))
      (node (ref "D3") (pin "2") (pinfunction "A_2") (pintype "passive"))
      (node (ref "L_POS") (pin "1") (pinfunction "1_1") (pintype "passive"))
      (node (ref "L_POS") (pin "2") (pinfunction "1_2") (pintype "passive"))
      (node (ref "Q5") (pin "3") (pinfunction "S_3") (pintype "bidirectional"))
      (node (ref "Q6") (pin "3") (pinfunction "S_3") (pintype "bidirectional"))
    )
    (net (code "15") (name "Net-(D3-C)") (class "Default")
      (node (ref "D3") (pin "1") (pinfunction "C_1") (pintype "passive"))
      (node (ref "Q1") (pin "2") (pinfunction "D_2") (pintype "bidirectional"))
    )
    (net (code "16") (name "Net-(D4-C)") (class "Default")
      (node (ref "D4") (pin "1") (pinfunction "C_1") (pintype "passive"))
      (node (ref "Q5") (pin "2") (pinfunction "D_2") (pintype "bidirectional"))
    )
    (net (code "17") (name "Net-(D5-A)") (class "Default")
      (node (ref "D5") (pin "2") (pinfunction "A_2") (pintype "passive"))
      (node (ref "Q6") (pin "2") (pinfunction "D_2") (pintype "bidirectional"))
    )
    (net (code "18") (name "Net-(D7-C)") (class "Default")
      (node (ref "D10") (pin "A") (pinfunction "A_A") (pintype "passive"))
      (node (ref "D7") (pin "K") (pinfunction "C_K") (pintype "passive"))
      (node (ref "R61") (pin "1") (pinfunction "1_1") (pintype "passive"))
      (node (ref "U12") (pin "3") (pinfunction "OUT_3") (pintype "output"))
    )
    (net (code "19") (name "Net-(D8-C)") (class "Default")
      (node (ref "D6") (pin "A") (pinfunction "A_A") (pintype "passive"))
      (node (ref "D8") (pin "K") (pinfunction "C_K") (pintype "passive"))
      (node (ref "R64") (pin "1") (pinfunction "1_1") (pintype "passive"))
      (node (ref "U3") (pin "1") (pinfunction "OUT_1") (pintype "output"))
    )
    (net (code "20") (name "Net-(D11-C)") (class "Default")
      (node (ref "D11") (pin "K") (pinfunction "C_K") (pintype "passive"))
      (node (ref "D9") (pin "A") (pinfunction "A_A") (pintype "passive"))
      (node (ref "R65") (pin "1") (pinfunction "1_1") (pintype "passive"))
      (node (ref "U4") (pin "1") (pinfunction "OUT_1") (pintype "output"))
    )
    (net (code "21") (name "Net-(DB-COMMON)") (class "Default")
      (node (ref "CD") (pin "2") (pinfunction "2_2") (pintype "passive"))
      (node (ref "D") (pin "2") (pinfunction "COMMON_2") (pintype "passive"))
      (node (ref "R4") (pin "1") (pinfunction "CCW_1") (pintype "passive"))
      (node (ref "R4") (pin "2") (pinfunction "WIPER_2") (pintype "passive"))
      (node (ref "U8") (pin "6") (pinfunction "-IN_6") (pintype "input"))
    )
    (net (code "22") (name "Net-(DB-NO)") (class "Default")
      (node (ref "D") (pin "3") (pinfunction "NO_3") (pintype "passive"))
      (node (ref "R15") (pin "1") (pinfunction "1_1") (pintype "passive"))
      (node (ref "R4") (pin "3") (pinfunction "CW_3") (pintype "passive"))
      (node (ref "U8") (pin "7") (pinfunction "OUT_7") (pintype "output"))
    )
    (net (code "23") (name "Net-(IB-COMMON)") (class "Default")
      (node (ref "CI") (pin "1") (pinfunction "1_1") (pintype "passive"))
      (node (ref "I") (pin "2") (pinfunction "COMMON_2") (pintype "passive"))
      (node (ref "R3") (pin "1") (pinfunction "CCW_1") (pintype "passive"))
      (node (ref "R49") (pin "1") (pinfunction "1_1") (pintype "passive"))
      (node (ref "U8") (pin "11") (pinfunction "-IN_11") (pintype "input"))
    )
    (net (code "24") (name "Net-(IB-NO)") (class "Default")
      (node (ref "CI") (pin "2") (pinfunction "2_2") (pintype "passive"))
      (node (ref "I") (pin "3") (pinfunction "NO_3") (pintype "passive"))
      (node (ref "R36") (pin "1") (pinfunction "1_1") (pintype "passive"))
      (node (ref "R49") (pin "2") (pinfunction "2_2") (pintype "passive"))
      (node (ref "U8") (pin "10") (pinfunction "OUT_10") (pintype "output"))
    )
    (net (code "25") (name "Net-(P1-H-Pad1)") (class "Default")
      (node (ref "P1") (pin "1") (pinfunction "H_1") (pintype "passive"))
      (node (ref "P1") (pin "2") (pinfunction "H_2") (pintype "passive"))
      (node (ref "P1") (pin "3") (pinfunction "H_3") (pintype "passive"))
      (node (ref "P1") (pin "4") (pinfunction "H_4") (pintype "passive"))
      (node (ref "P1") (pin "5") (pinfunction "H_5") (pintype "passive"))
      (node (ref "P1") (pin "6") (pinfunction "H_6") (pintype "passive"))
      (node (ref "P1") (pin "7") (pinfunction "H_7") (pintype "passive"))
      (node (ref "P1") (pin "8") (pinfunction "H_8") (pintype "passive"))
      (node (ref "P1") (pin "P") (pinfunction "P_P") (pintype "passive"))
    )
    (net (code "26") (name "Net-(P2-H-Pad1)") (class "Default")
      (node (ref "P2") (pin "1") (pinfunction "H_1") (pintype "passive"))
      (node (ref "P2") (pin "2") (pinfunction "H_2") (pintype "passive"))
      (node (ref "P2") (pin "3") (pinfunction "H_3") (pintype "passive"))
      (node (ref "P2") (pin "4") (pinfunction "H_4") (pintype "passive"))
      (node (ref "P2") (pin "5") (pinfunction "H_5") (pintype "passive"))
      (node (ref "P2") (pin "6") (pinfunction "H_6") (pintype "passive"))
      (node (ref "P2") (pin "7") (pinfunction "H_7") (pintype "passive"))
      (node (ref "P2") (pin "8") (pinfunction "H_8") (pintype "passive"))
      (node (ref "P2") (pin "P") (pinfunction "P_P") (pintype "passive"))
    )
    (net (code "27") (name "Net-(P3-H-Pad1)") (class "Default")
      (node (ref "P3") (pin "1") (pinfunction "H_1") (pintype "passive"))
      (node (ref "P3") (pin "2") (pinfunction "H_2") (pintype "passive"))
      (node (ref "P3") (pin "3") (pinfunction "H_3") (pintype "passive"))
      (node (ref "P3") (pin "4") (pinfunction "H_4") (pintype "passive"))
      (node (ref "P3") (pin "5") (pinfunction "H_5") (pintype "passive"))
      (node (ref "P3") (pin "6") (pinfunction "H_6") (pintype "passive"))
      (node (ref "P3") (pin "7") (pinfunction "H_7") (pintype "passive"))
      (node (ref "P3") (pin "8") (pinfunction "H_8") (pintype "passive"))
      (node (ref "P3") (pin "P") (pinfunction "P_P") (pintype "passive"))
    )
    (net (code "28") (name "Net-(P4-H-Pad1)") (class "Default")
      (node (ref "P4") (pin "1") (pinfunction "H_1") (pintype "passive"))
      (node (ref "P4") (pin "2") (pinfunction "H_2") (pintype "passive"))
      (node (ref "P4") (pin "3") (pinfunction "H_3") (pintype "passive"))
      (node (ref "P4") (pin "4") (pinfunction "H_4") (pintype "passive"))
      (node (ref "P4") (pin "5") (pinfunction "H_5") (pintype "passive"))
      (node (ref "P4") (pin "6") (pinfunction "H_6") (pintype "passive"))
      (node (ref "P4") (pin "7") (pinfunction "H_7") (pintype "passive"))
      (node (ref "P4") (pin "8") (pinfunction "H_8") (pintype "passive"))
      (node (ref "P4") (pin "P") (pinfunction "P_P") (pintype "passive"))
    )
    (net (code "29") (name "Net-(PB-COMMON)") (class "Default")
      (node (ref "P") (pin "2") (pinfunction "COMMON_2") (pintype "passive"))
      (node (ref "R1") (pin "2") (pinfunction "WIPER_2") (pintype "passive"))
      (node (ref "R1") (pin "3") (pinfunction "CW_3") (pintype "passive"))
      (node (ref "R12") (pin "2") (pinfunction "2_2") (pintype "passive"))
      (node (ref "U8") (pin "15") (pinfunction "-IN_15") (pintype "input"))
    )
    (net (code "30") (name "Net-(PB-NO)") (class "Default")
      (node (ref "P") (pin "3") (pinfunction "NO_3") (pintype "passive"))
      (node (ref "R1") (pin "1") (pinfunction "CCW_1") (pintype "passive"))
      (node (ref "R11") (pin "1") (pinfunction "1_1") (pintype "passive"))
      (node (ref "U8") (pin "16") (pinfunction "OUT_16") (pintype "output"))
    )
    (net (code "31") (name "Net-(Q1-G)") (class "Default")
      (node (ref "Q1") (pin "1") (pinfunction "G_1") (pintype "bidirectional"))
      (node (ref "R24") (pin "2") (pinfunction "2_2") (pintype "passive"))
    )
    (net (code "32") (name "Net-(Q1-S)") (class "Default")
      (node (ref "CAP_HV_NEG") (pin "1") (pinfunction "1_1") (pintype "passive"))
      (node (ref "CAP_HV_NEG") (pin "2") (pinfunction "1_2") (pintype "passive"))
      (node (ref "Q1") (pin "3") (pinfunction "S_3") (pintype "bidirectional"))
      (node (ref "R26") (pin "2") (pinfunction "2_2") (pintype "passive"))
    )
    (net (code "33") (name "Net-(Q2-G)") (class "Default")
      (node (ref "Q2") (pin "1") (pinfunction "G_1") (pintype "bidirectional"))
      (node (ref "R18") (pin "2") (pinfunction "2_2") (pintype "passive"))
    )
    (net (code "34") (name "Net-(Q2-S)") (class "Default")
      (node (ref "CAP_HV_POS") (pin "1") (pinfunction "1_1") (pintype "passive"))
      (node (ref "CAP_HV_POS") (pin "2") (pinfunction "1_2") (pintype "passive"))
      (node (ref "Q2") (pin "3") (pinfunction "S_3") (pintype "bidirectional"))
      (node (ref "R30") (pin "2") (pinfunction "2_2") (pintype "passive"))
    )
    (net (code "35") (name "Net-(Q3-B)") (class "Default")
      (node (ref "Q3") (pin "1") (pinfunction "B_1") (pintype "passive"))
      (node (ref "R14") (pin "2") (pinfunction "2_2") (pintype "passive"))
    )
    (net (code "36") (name "Net-(Q3-C)") (class "Default")
      (node (ref "Q3") (pin "3") (pinfunction "C_3") (pintype "passive"))
      (node (ref "R16") (pin "1") (pinfunction "1_1") (pintype "passive"))
      (node (ref "R18") (pin "1") (pinfunction "1_1") (pintype "passive"))
    )
    (net (code "37") (name "Net-(Q4-B)") (class "Default")
      (node (ref "Q4") (pin "1") (pinfunction "B_1") (pintype "passive"))
      (node (ref "R27") (pin "2") (pinfunction "2_2") (pintype "passive"))
    )
    (net (code "38") (name "Net-(Q4-C)") (class "Default")
      (node (ref "Q4") (pin "3") (pinfunction "C_3") (pintype "passive"))
      (node (ref "R24") (pin "1") (pinfunction "1_1") (pintype "passive"))
      (node (ref "R25") (pin "2") (pinfunction "2_2") (pintype "passive"))
    )
    (net (code "39") (name "Net-(Q5-G)") (class "Default")
      (node (ref "Q5") (pin "1") (pinfunction "G_1") (pintype "bidirectional"))
      (node (ref "R39") (pin "1") (pinfunction "1_1") (pintype "passive"))
    )
    (net (code "40") (name "Net-(Q6-G)") (class "Default")
      (node (ref "Q6") (pin "1") (pinfunction "G_1") (pintype "bidirectional"))
      (node (ref "R44") (pin "1") (pinfunction "1_1") (pintype "passive"))
    )
    (net (code "41") (name "Net-(R3-CW)") (class "Default")
      (node (ref "R17") (pin "2") (pinfunction "2_2") (pintype "passive"))
      (node (ref "R3") (pin "2") (pinfunction "WIPER_2") (pintype "passive"))
      (node (ref "R3") (pin "3") (pinfunction "CW_3") (pintype "passive"))
    )
    (net (code "42") (name "Net-(R5-CCW)") (class "Default")
      (node (ref "R47") (pin "2") (pinfunction "2_2") (pintype "passive"))
      (node (ref "R5") (pin "1") (pinfunction "CCW_1") (pintype "passive"))
      (node (ref "U7") (pin "16") (pinfunction "OUT_16") (pintype "output"))
    )
    (net (code "43") (name "Net-(R5-WIPER)") (class "Default")
      (node (ref "R21") (pin "1") (pinfunction "1_1") (pintype "passive"))
      (node (ref "R5") (pin "2") (pinfunction "WIPER_2") (pintype "passive"))
    )
    (net (code "44") (name "Net-(R6-CCW)") (class "Default")
      (node (ref "R32") (pin "2") (pinfunction "2_2") (pintype "passive"))
      (node (ref "R6") (pin "1") (pinfunction "CCW_1") (pintype "passive"))
      (node (ref "U7") (pin "10") (pinfunction "OUT_10") (pintype "output"))
    )
    (net (code "45") (name "Net-(R6-WIPER)") (class "Default")
      (node (ref "R29") (pin "1") (pinfunction "1_1") (pintype "passive"))
      (node (ref "R6") (pin "2") (pinfunction "WIPER_2") (pintype "passive"))
    )
    (net (code "46") (name "Net-(R19-CCW)") (class "Default")
      (node (ref "R14") (pin "1") (pinfunction "1_1") (pintype "passive"))
      (node (ref "R19") (pin "1") (pinfunction "CCW_1") (pintype "passive"))
      (node (ref "R27") (pin "1") (pinfunction "1_1") (pintype "passive"))
      (node (ref "U2") (pin "16") (pinfunction "OUT_16") (pintype "output"))
    )
    (net (code "47") (name "Net-(R19-CW)") (class "Default")
      (node (ref "R19") (pin "2") (pinfunction "WIPER_2") (pintype "passive"))
      (node (ref "R19") (pin "3") (pinfunction "CW_3") (pintype "passive"))
      (node (ref "R58") (pin "2") (pinfunction "2_2") (pintype "passive"))
      (node (ref "U2") (pin "15") (pinfunction "-IN_15") (pintype "input"))
    )
    (net (code "48") (name "Net-(R52-WIPER)") (class "Default")
      (node (ref "R51") (pin "2") (pinfunction "2_2") (pintype "passive"))
      (node (ref "R52") (pin "2") (pinfunction "WIPER_2") (pintype "passive"))
    )
    (net (code "49") (name "Net-(R57-WIPER)") (class "Default")
      (node (ref "R56") (pin "2") (pinfunction "2_2") (pintype "passive"))
      (node (ref "R57") (pin "2") (pinfunction "WIPER_2") (pintype "passive"))
    )
    (net (code "50") (name "Net-(SP/SENSEB-1)") (class "Default")
      (node (ref "C18") (pin "2") (pinfunction "2_2") (pintype "passive"))
      (node (ref "R42") (pin "2") (pinfunction "2_2") (pintype "passive"))
      (node (ref "R45") (pin "1") (pinfunction "1_1") (pintype "passive"))
      (node (ref "R8") (pin "2") (pinfunction "2_2") (pintype "passive"))
      (node (ref "SP/SENSE") (pin "3") (pinfunction "1_3") (pintype "passive"))
      (node (ref "U7") (pin "1") (pinfunction "OUT_1") (pintype "output"))
    )
    (net (code "51") (name "Net-(U1-IP+_1)") (class "Default")
      (node (ref "L_GND") (pin "1") (pinfunction "1_1") (pintype "passive"))
      (node (ref "L_GND") (pin "2") (pinfunction "1_2") (pintype "passive"))
      (node (ref "U1") (pin "1") (pinfunction "IP+_1_1") (pintype "bidirectional"))
      (node (ref "U1") (pin "2") (pinfunction "IP+_2_2") (pintype "bidirectional"))
      (node (ref "U1") (pin "3") (pinfunction "IP+_3_3") (pintype "bidirectional"))
      (node (ref "U1") (pin "4") (pinfunction "IP+_4_4") (pintype "bidirectional"))
    )
    (net (code "52") (name "Net-(U1-IP-_1)") (class "Default")
      (node (ref "LV_GND") (pin "1") (pinfunction "1_1") (pintype "passive"))
      (node (ref "LV_GND") (pin "2") (pinfunction "1_2") (pintype "passive"))
      (node (ref "U1") (pin "5") (pinfunction "IP-_1_5") (pintype "bidirectional"))
      (node (ref "U1") (pin "6") (pinfunction "IP-_2_6") (pintype "bidirectional"))
      (node (ref "U1") (pin "7") (pinfunction "IP-_3_7") (pintype "bidirectional"))
      (node (ref "U1") (pin "8") (pinfunction "IP-_4_8") (pintype "bidirectional"))
    )
    (net (code "53") (name "Net-(U1-VOC)") (class "Default")
      (node (ref "R13") (pin "1") (pinfunction "1_1") (pintype "passive"))
      (node (ref "U1") (pin "16") (pinfunction "VOC_16") (pintype "bidirectional"))
    )
    (net (code "54") (name "Net-(U1-VOUT)") (class "Default")
      (node (ref "R7") (pin "1") (pinfunction "1_1") (pintype "passive"))
      (node (ref "U1") (pin "12") (pinfunction "VOUT_12") (pintype "bidirectional"))
    )
    (net (code "55") (name "Net-(U1-VREF)") (class "Default")
      (node (ref "R2") (pin "1") (pinfunction "1_1") (pintype "passive"))
      (node (ref "U1") (pin "13") (pinfunction "VREF_13") (pintype "bidirectional"))
    )
    (net (code "56") (name "Net-(U1-~{FAULTB})") (class "Default")
      (node (ref "R10") (pin "1") (pinfunction "1_1") (pintype "passive"))
      (node (ref "U1") (pin "9") (pinfunction "~{FAULTB}_9") (pintype "bidirectional"))
    )
    (net (code "57") (name "Net-(U2A-+IN)") (class "Default")
      (node (ref "C21") (pin "2") (pinfunction "2_2") (pintype "passive"))
      (node (ref "R34") (pin "2") (pinfunction "2_2") (pintype "passive"))
      (node (ref "U2") (pin "3") (pinfunction "+IN_3") (pintype "input"))
      (node (ref "U8") (pin "1") (pinfunction "OUT_1") (pintype "output"))
    )
    (net (code "58") (name "Net-(U2A--IN)") (class "Default")
      (node (ref "R20") (pin "2") (pinfunction "2_2") (pintype "passive"))
      (node (ref "R23") (pin "2") (pinfunction "2_2") (pintype "passive"))
      (node (ref "U2") (pin "2") (pinfunction "-IN_2") (pintype "input"))
    )
    (net (code "59") (name "Net-(U2A-OUT)") (class "Default")
      (node (ref "R20") (pin "1") (pinfunction "1_1") (pintype "passive"))
      (node (ref "R48") (pin "2") (pinfunction "2_2") (pintype "passive"))
      (node (ref "R54") (pin "2") (pinfunction "2_2") (pintype "passive"))
      (node (ref "U2") (pin "1") (pinfunction "OUT_1") (pintype "output"))
    )
    (net (code "60") (name "Net-(U2B-+IN)") (class "Default")
      (node (ref "R55") (pin "1") (pinfunction "1_1") (pintype "passive"))
      (node (ref "R56") (pin "1") (pinfunction "1_1") (pintype "passive"))
      (node (ref "U2") (pin "5") (pinfunction "+IN_5") (pintype "input"))
    )
    (net (code "61") (name "Net-(U2B--IN)") (class "Default")
      (node (ref "C11") (pin "1") (pinfunction "1_1") (pintype "passive"))
      (node (ref "C8") (pin "1") (pinfunction "1_1") (pintype "passive"))
      (node (ref "R53") (pin "2") (pinfunction "2_2") (pintype "passive"))
      (node (ref "R54") (pin "1") (pinfunction "1_1") (pintype "passive"))
      (node (ref "U2") (pin "6") (pinfunction "-IN_6") (pintype "input"))
    )
    (net (code "62") (name "Net-(U2B-OUT)") (class "Default")
      (node (ref "C8") (pin "2") (pinfunction "2_2") (pintype "passive"))
      (node (ref "R40") (pin "2") (pinfunction "2_2") (pintype "passive"))
      (node (ref "U2") (pin "7") (pinfunction "OUT_7") (pintype "output"))
      (node (ref "U6") (pin "3") (pinfunction "IN_3") (pintype "input"))
    )
    (net (code "63") (name "Net-(U2C-+IN)") (class "Default")
      (node (ref "R50") (pin "1") (pinfunction "1_1") (pintype "passive"))
      (node (ref "R51") (pin "1") (pinfunction "1_1") (pintype "passive"))
      (node (ref "U2") (pin "12") (pinfunction "+IN_12") (pintype "input"))
    )
    (net (code "64") (name "Net-(U2C--IN)") (class "Default")
      (node (ref "C10") (pin "1") (pinfunction "1_1") (pintype "passive"))
      (node (ref "C9") (pin "1") (pinfunction "1_1") (pintype "passive"))
      (node (ref "R46") (pin "2") (pinfunction "2_2") (pintype "passive"))
      (node (ref "R48") (pin "1") (pinfunction "1_1") (pintype "passive"))
      (node (ref "U2") (pin "11") (pinfunction "-IN_11") (pintype "input"))
    )
    (net (code "65") (name "Net-(U2C-OUT)") (class "Default")
      (node (ref "C9") (pin "2") (pinfunction "2_2") (pintype "passive"))
      (node (ref "R59") (pin "2") (pinfunction "2_2") (pintype "passive"))
      (node (ref "U2") (pin "10") (pinfunction "OUT_10") (pintype "output"))
      (node (ref "U5") (pin "3") (pinfunction "IN_3") (pintype "input"))
    )
    (net (code "66") (name "Net-(U5A-BW)") (class "Default")
      (node (ref "R31") (pin "1") (pinfunction "1_1") (pintype "passive"))
      (node (ref "U5") (pin "1") (pinfunction "BW_1") (pintype "input"))
    )
    (net (code "67") (name "Net-(U5A-OUT)") (class "Default")
      (node (ref "C10") (pin "2") (pinfunction "2_2") (pintype "passive"))
      (node (ref "R39") (pin "2") (pinfunction "2_2") (pintype "passive"))
      (node (ref "R46") (pin "1") (pinfunction "1_1") (pintype "passive"))
      (node (ref "R59") (pin "1") (pinfunction "1_1") (pintype "passive"))
      (node (ref "U5") (pin "6") (pinfunction "OUT_6") (pintype "output"))
    )
    (net (code "68") (name "Net-(U6A-BW)") (class "Default")
      (node (ref "R37") (pin "1") (pinfunction "1_1") (pintype "passive"))
      (node (ref "U6") (pin "1") (pinfunction "BW_1") (pintype "input"))
    )
    (net (code "69") (name "Net-(U6A-OUT)") (class "Default")
      (node (ref "C11") (pin "2") (pinfunction "2_2") (pintype "passive"))
      (node (ref "R40") (pin "1") (pinfunction "1_1") (pintype "passive"))
      (node (ref "R44") (pin "2") (pinfunction "2_2") (pintype "passive"))
      (node (ref "R53") (pin "1") (pinfunction "1_1") (pintype "passive"))
      (node (ref "U6") (pin "6") (pinfunction "OUT_6") (pintype "output"))
    )
    (net (code "70") (name "Net-(U7A-+IN)") (class "Default")
      (node (ref "R7") (pin "2") (pinfunction "2_2") (pintype "passive"))
      (node (ref "R9") (pin "2") (pinfunction "2_2") (pintype "passive"))
      (node (ref "U7") (pin "3") (pinfunction "+IN_3") (pintype "input"))
    )
    (net (code "71") (name "Net-(U7A--IN)") (class "Default")
      (node (ref "C18") (pin "1") (pinfunction "1_1") (pintype "passive"))
      (node (ref "R2") (pin "2") (pinfunction "2_2") (pintype "passive"))
      (node (ref "R8") (pin "1") (pinfunction "1_1") (pintype "passive"))
      (node (ref "U7") (pin "2") (pinfunction "-IN_2") (pintype "input"))
    )
    (net (code "72") (name "Net-(U7B--IN)") (class "Default")
      (node (ref "C28") (pin "1") (pinfunction "1_1") (pintype "passive"))
      (node (ref "R21") (pin "2") (pinfunction "2_2") (pintype "passive"))
      (node (ref "R29") (pin "2") (pinfunction "2_2") (pintype "passive"))
      (node (ref "R43") (pin "1") (pinfunction "1_1") (pintype "passive"))
      (node (ref "U7") (pin "6") (pinfunction "-IN_6") (pintype "input"))
    )
    (net (code "73") (name "Net-(U7B-OUT)") (class "Default")
      (node (ref "C28") (pin "2") (pinfunction "2_2") (pintype "passive"))
      (node (ref "R12") (pin "1") (pinfunction "1_1") (pintype "passive"))
      (node (ref "R17") (pin "1") (pinfunction "1_1") (pintype "passive"))
      (node (ref "R22") (pin "1") (pinfunction "1_1") (pintype "passive"))
      (node (ref "R43") (pin "2") (pinfunction "2_2") (pintype "passive"))
      (node (ref "R58") (pin "1") (pinfunction "1_1") (pintype "passive"))
      (node (ref "U7") (pin "7") (pinfunction "OUT_7") (pintype "output"))
    )
    (net (code "74") (name "Net-(U7C-+IN)") (class "Default")
      (node (ref "R38") (pin "2") (pinfunction "2_2") (pintype "passive"))
      (node (ref "SP/SENSE") (pin "1") (pinfunction "1_1") (pintype "passive"))
      (node (ref "U7") (pin "12") (pinfunction "+IN_12") (pintype "input"))
    )
    (net (code "75") (name "Net-(U7C--IN)") (class "Default")
      (node (ref "R32") (pin "1") (pinfunction "1_1") (pintype "passive"))
      (node (ref "R35") (pin "2") (pinfunction "2_2") (pintype "passive"))
      (node (ref "U7") (pin "11") (pinfunction "-IN_11") (pintype "input"))
    )
    (net (code "76") (name "Net-(U7D-+IN)") (class "Default")
      (node (ref "R41") (pin "2") (pinfunction "2_2") (pintype "passive"))
      (node (ref "U7") (pin "14") (pinfunction "+IN_14") (pintype "input"))
    )
    (net (code "77") (name "Net-(U7D--IN)") (class "Default")
      (node (ref "R45") (pin "2") (pinfunction "2_2") (pintype "passive"))
      (node (ref "R47") (pin "1") (pinfunction "1_1") (pintype "passive"))
      (node (ref "U7") (pin "15") (pinfunction "-IN_15") (pintype "input"))
    )
    (net (code "78") (name "Net-(U8A--IN)") (class "Default")
      (node (ref "C21") (pin "1") (pinfunction "1_1") (pintype "passive"))
      (node (ref "R11") (pin "2") (pinfunction "2_2") (pintype "passive"))
      (node (ref "R15") (pin "2") (pinfunction "2_2") (pintype "passive"))
      (node (ref "R34") (pin "1") (pinfunction "1_1") (pintype "passive"))
      (node (ref "R36") (pin "2") (pinfunction "2_2") (pintype "passive"))
      (node (ref "U8") (pin "2") (pinfunction "-IN_2") (pintype "input"))
    )
    (net (code "79") (name "unconnected-(DB-NC-Pad1)") (class "Default")
      (node (ref "D") (pin "1") (pinfunction "NC_1") (pintype "passive"))
    )
    (net (code "80") (name "unconnected-(HS1-PIN-Pad1)") (class "Default")
      (node (ref "HS1") (pin "1") (pinfunction "PIN_1") (pintype "bidirectional"))
    )
    (net (code "81") (name "unconnected-(HS2-PIN-Pad1)") (class "Default")
      (node (ref "HS2") (pin "1") (pinfunction "PIN_1") (pintype "bidirectional"))
    )
    (net (code "82") (name "unconnected-(IB-NC-Pad1)") (class "Default")
      (node (ref "I") (pin "1") (pinfunction "NC_1") (pintype "passive"))
    )
    (net (code "83") (name "unconnected-(PB-NC-Pad1)") (class "Default")
      (node (ref "P") (pin "1") (pinfunction "NC_1") (pintype "passive"))
    )
  )
)
